# audioProto_v1.net
KiCad netlist of a schematic drawn in EAGLE
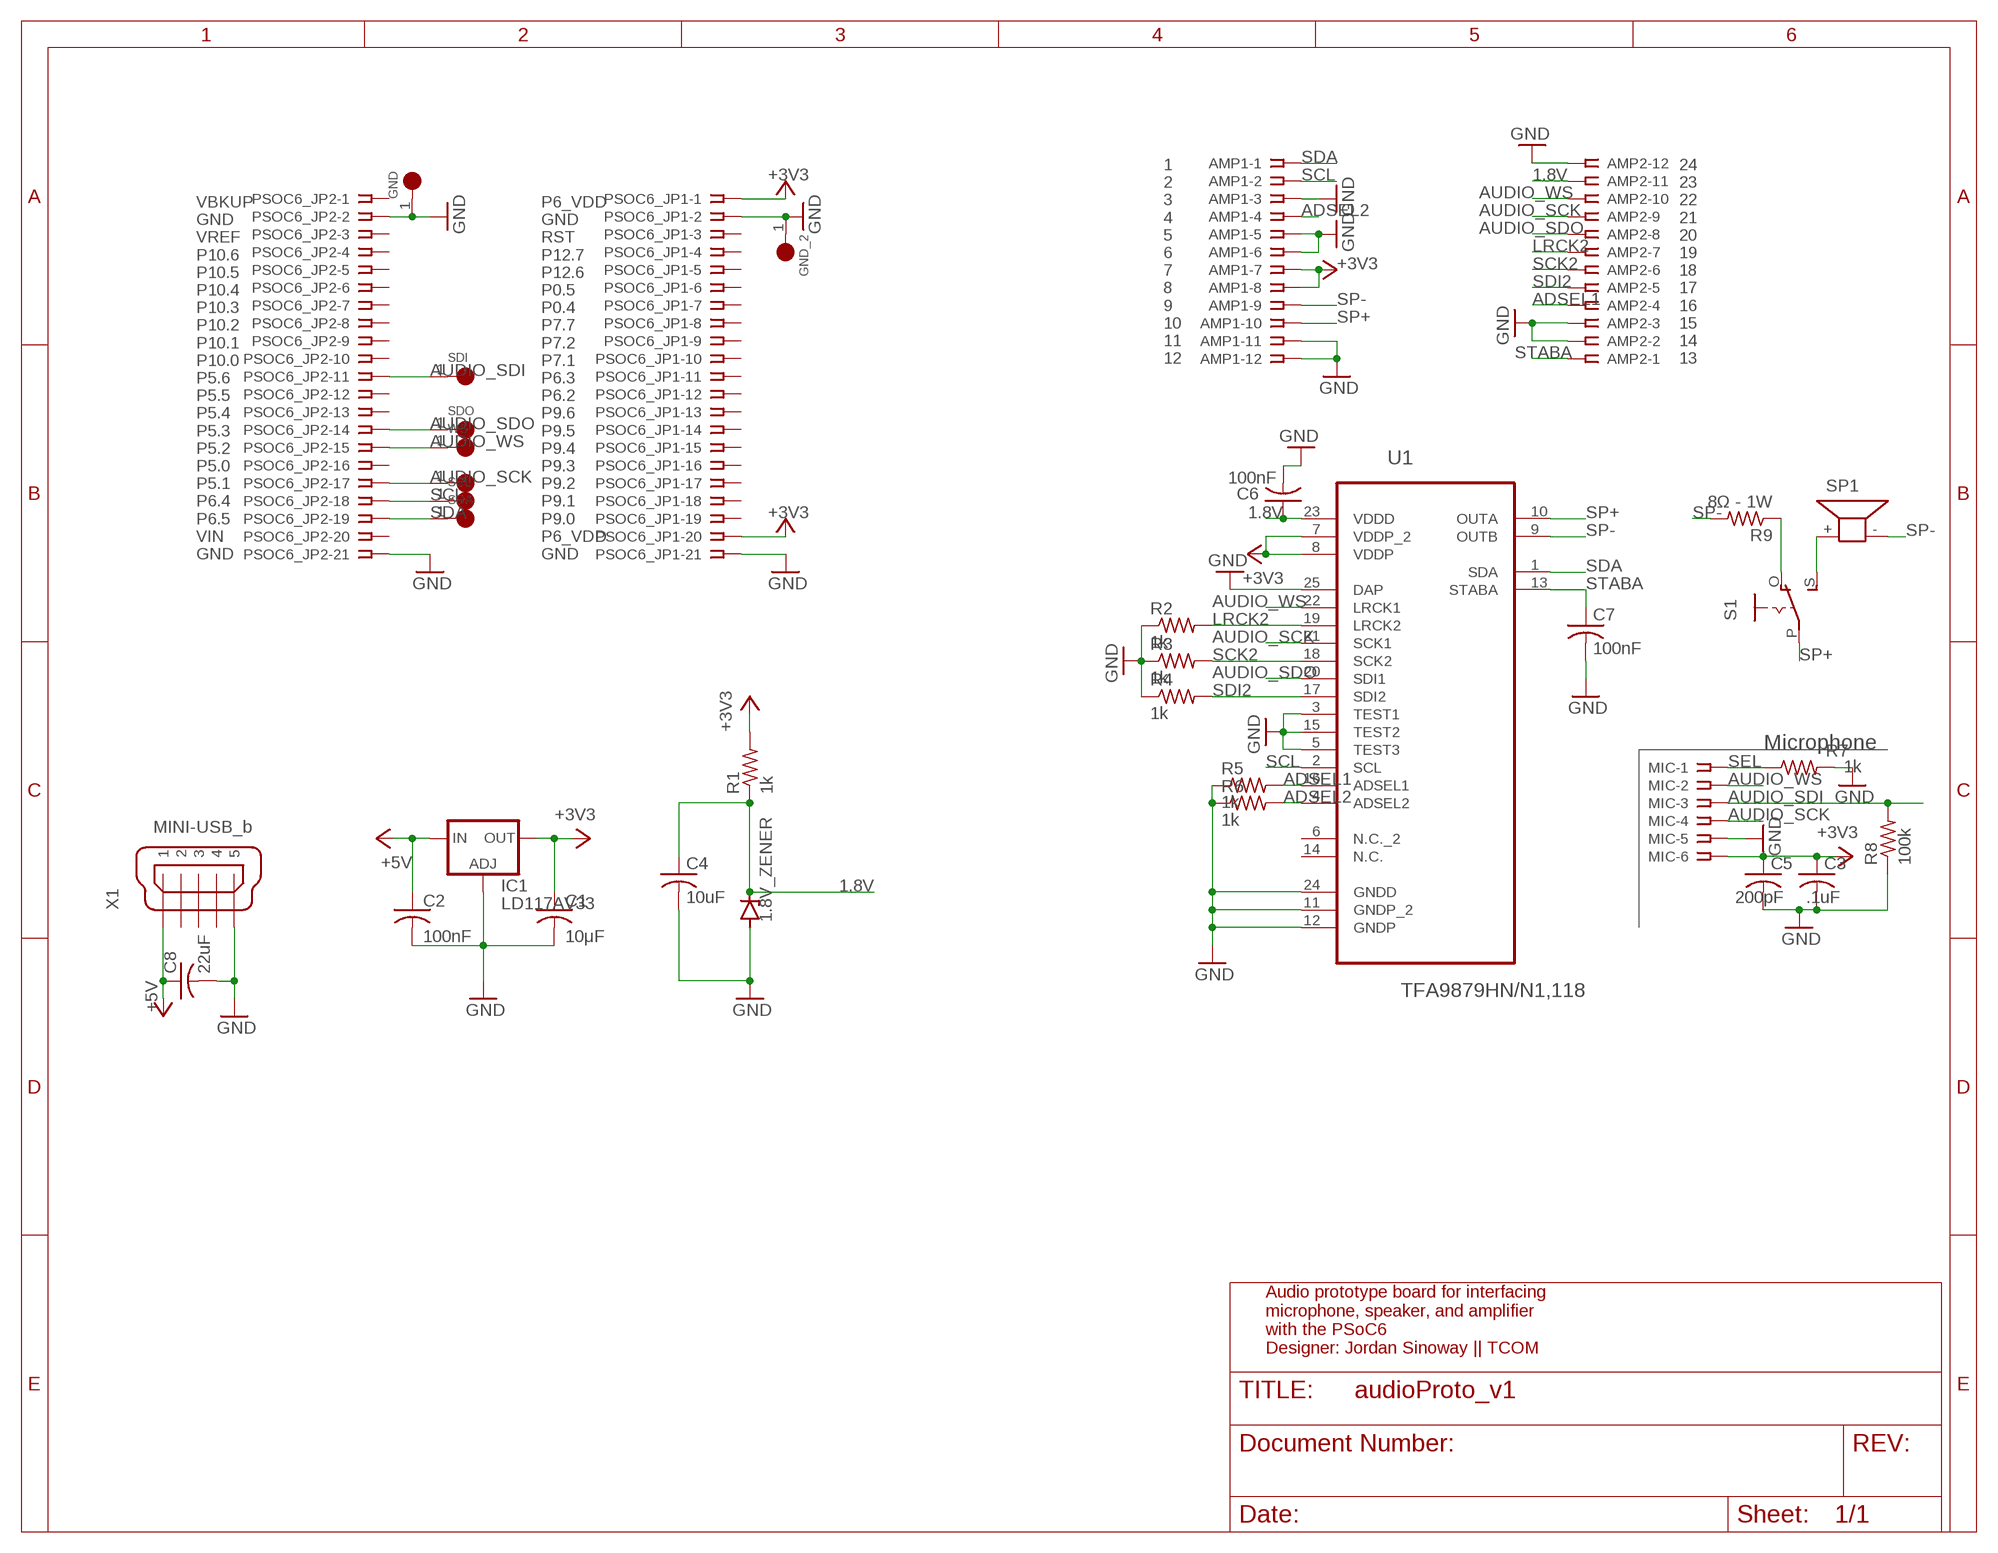
[diagram p0: schematic, sheet 1]

(export (version "E")
  (design (tool "Eeschema 10.0.6"))
  (components
    (comp (ref "1.8V_ZENER")
      (value "BZV10")
      (footprint "eagle-import:DO34Z7")
      (libsource (lib "eagle-import") (part "BZV10"))
    )
    (comp (ref "AMP1")
      (value "SSW-112-02-G-S")
      (footprint "eagle-import:SSW-112-02-G-S")
      (fields (field (name "MF") "Samtec Inc."))
      (libsource (lib "eagle-import") (part "SSW-112-02-G-S"))
    )
    (comp (ref "AMP2")
      (value "SSW-112-02-G-S")
      (footprint "eagle-import:SSW-112-02-G-S")
      (fields (field (name "MF") "Samtec Inc."))
      (libsource (lib "eagle-import") (part "SSW-112-02-G-S"))
    )
    (comp (ref "C1")
      (value "10μF")
      (footprint "eagle-import:C050-024X044")
      (libsource (lib "eagle-import") (part "C-US050-024X044"))
    )
    (comp (ref "C2")
      (value "100nF")
      (footprint "eagle-import:C050-024X044")
      (libsource (lib "eagle-import") (part "C-US050-024X044"))
    )
    (comp (ref "C3")
      (value ".1uF")
      (footprint "eagle-import:C050-024X044")
      (libsource (lib "eagle-import") (part "C-US050-024X044"))
    )
    (comp (ref "C4")
      (value "10uF")
      (footprint "eagle-import:C050-024X044")
      (libsource (lib "eagle-import") (part "C-US050-024X044"))
    )
    (comp (ref "C5")
      (value "200pF")
      (footprint "eagle-import:C050-024X044")
      (libsource (lib "eagle-import") (part "C-US050-024X044"))
    )
    (comp (ref "C6")
      (value "100nF")
      (footprint "eagle-import:C050-024X044")
      (libsource (lib "eagle-import") (part "C-US050-024X044"))
    )
    (comp (ref "C7")
      (value "100nF")
      (footprint "eagle-import:C050-024X044")
      (libsource (lib "eagle-import") (part "C-US050-024X044"))
    )
    (comp (ref "C8")
      (value "22uF")
      (footprint "eagle-import:C050-024X044")
      (libsource (lib "eagle-import") (part "C-US050-024X044"))
    )
    (comp (ref "GND")
      (value "5013")
      (footprint "eagle-import:TESTPOINT_5013")
      (fields (field (name "MF") "Keystone Electronics"))
      (libsource (lib "eagle-import") (part "5013"))
    )
    (comp (ref "GND_2")
      (value "5013")
      (footprint "eagle-import:TESTPOINT_5013")
      (fields (field (name "MF") "Keystone Electronics"))
      (libsource (lib "eagle-import") (part "5013"))
    )
    (comp (ref "IC1")
      (value "LD117AV33")
      (footprint "eagle-import:TO220L1")
      (libsource (lib "eagle-import") (part "LD117A?V33"))
    )
    (comp (ref "MIC")
      (value "SSW-106-02-G-S")
      (footprint "eagle-import:SSW-106-02-G-S")
      (fields (field (name "MF") "Samtec Inc."))
      (libsource (lib "eagle-import") (part "SSW-106-02-G-S"))
    )
    (comp (ref "PSOC6_JP1")
      (value "SSW-121-02-G-S")
      (footprint "eagle-import:SSW-121-02-G-S")
      (fields (field (name "MF") "Samtec Inc."))
      (libsource (lib "eagle-import") (part "SSW-121-02-G-S"))
    )
    (comp (ref "PSOC6_JP2")
      (value "SSW-121-02-G-S")
      (footprint "eagle-import:SSW-121-02-G-S")
      (fields (field (name "MF") "Samtec Inc."))
      (libsource (lib "eagle-import") (part "SSW-121-02-G-S"))
    )
    (comp (ref "R1")
      (value "1k")
      (footprint "eagle-import:0204_7")
      (libsource (lib "eagle-import") (part "R-US_0204/7"))
    )
    (comp (ref "R2")
      (value "1k")
      (footprint "eagle-import:0204_7")
      (libsource (lib "eagle-import") (part "R-US_0204/7"))
    )
    (comp (ref "R3")
      (value "1k")
      (footprint "eagle-import:0204_7")
      (libsource (lib "eagle-import") (part "R-US_0204/7"))
    )
    (comp (ref "R4")
      (value "1k")
      (footprint "eagle-import:0204_7")
      (libsource (lib "eagle-import") (part "R-US_0204/7"))
    )
    (comp (ref "R5")
      (value "1k")
      (footprint "eagle-import:0204_7")
      (libsource (lib "eagle-import") (part "R-US_0204/7"))
    )
    (comp (ref "R6")
      (value "1k")
      (footprint "eagle-import:0204_7")
      (libsource (lib "eagle-import") (part "R-US_0204/7"))
    )
    (comp (ref "R7")
      (value "1k")
      (footprint "eagle-import:0207_9")
      (libsource (lib "eagle-import") (part "R-US_0207/9"))
    )
    (comp (ref "R8")
      (value "100k")
      (footprint "eagle-import:0207_9")
      (libsource (lib "eagle-import") (part "R-US_0207/9"))
    )
    (comp (ref "R9")
      (value "8Ω - 1W")
      (footprint "eagle-import:0207_10")
      (libsource (lib "eagle-import") (part "R-US_0207/10"))
    )
    (comp (ref "S1")
      (value "EG1218S")
      (footprint "eagle-import:EG1218")
      (libsource (lib "eagle-import") (part "EG1218S"))
    )
    (comp (ref "SCK")
      (value "5013")
      (footprint "eagle-import:TESTPOINT_5013")
      (fields (field (name "MF") "Keystone Electronics"))
      (libsource (lib "eagle-import") (part "5013"))
    )
    (comp (ref "SCL")
      (value "5013")
      (footprint "eagle-import:TESTPOINT_5013")
      (fields (field (name "MF") "Keystone Electronics"))
      (libsource (lib "eagle-import") (part "5013"))
    )
    (comp (ref "SDA")
      (value "5013")
      (footprint "eagle-import:TESTPOINT_5013")
      (fields (field (name "MF") "Keystone Electronics"))
      (libsource (lib "eagle-import") (part "5013"))
    )
    (comp (ref "SDI")
      (value "5013")
      (footprint "eagle-import:TESTPOINT_5013")
      (fields (field (name "MF") "Keystone Electronics"))
      (libsource (lib "eagle-import") (part "5013"))
    )
    (comp (ref "SDO")
      (value "5013")
      (footprint "eagle-import:TESTPOINT_5013")
      (fields (field (name "MF") "Keystone Electronics"))
      (libsource (lib "eagle-import") (part "5013"))
    )
    (comp (ref "SP1")
      (value "KSS1201")
      (footprint "eagle-import:KSS1201")
      (libsource (lib "eagle-import") (part "KSS1201"))
    )
    (comp (ref "U1")
      (value "TFA9879HN/N1,118")
      (footprint "eagle-import:QFN50P260X260X100-25N")
      (fields (field (name "MF") "NXP USA"))
      (libsource (lib "eagle-import") (part "TFA9879HN/N1,118"))
    )
    (comp (ref "WS")
      (value "5013")
      (footprint "eagle-import:TESTPOINT_5013")
      (fields (field (name "MF") "Keystone Electronics"))
      (libsource (lib "eagle-import") (part "5013"))
    )
    (comp (ref "X1")
      (value "MINI-USB_b")
      (footprint "eagle-import:32005-601")
      (libsource (lib "eagle-import") (part "MINI-USB_SHIELD5P2-32005-601"))
    )
  )
  (nets
    (net (code "1") (name "+3V3") (class "Default")
      (node (ref "AMP1") (pin "7") (pinfunction "1_7") (pintype "passive"))
      (node (ref "AMP1") (pin "8") (pinfunction "1_8") (pintype "passive"))
      (node (ref "C1") (pin "1") (pinfunction "1_1") (pintype "passive"))
      (node (ref "C3") (pin "1") (pinfunction "1_1") (pintype "passive"))
      (node (ref "C5") (pin "1") (pinfunction "1_1") (pintype "passive"))
      (node (ref "IC1") (pin "2") (pinfunction "OUT_2") (pintype "passive"))
      (node (ref "MIC") (pin "6") (pinfunction "1_6") (pintype "passive"))
      (node (ref "PSOC6_JP1") (pin "1") (pinfunction "1_1") (pintype "passive"))
      (node (ref "PSOC6_JP1") (pin "20") (pinfunction "1_20") (pintype "passive"))
      (node (ref "R1") (pin "2") (pinfunction "2_2") (pintype "passive"))
      (node (ref "U1") (pin "7") (pinfunction "VDDP_2_7") (pintype "power_in"))
      (node (ref "U1") (pin "8") (pinfunction "VDDP_8") (pintype "power_in"))
    )
    (net (code "2") (name "+5V") (class "Default")
      (node (ref "C2") (pin "1") (pinfunction "1_1") (pintype "passive"))
      (node (ref "C8") (pin "1") (pinfunction "1_1") (pintype "passive"))
      (node (ref "IC1") (pin "3") (pinfunction "IN_3") (pintype "input"))
      (node (ref "X1") (pin "1") (pinfunction "1_1") (pintype "passive"))
    )
    (net (code "3") (name "/1.8V") (class "Default")
      (node (ref "1.8V_ZENER") (pin "C") (pinfunction "C_C") (pintype "passive"))
      (node (ref "AMP2") (pin "11") (pinfunction "1_11") (pintype "passive"))
      (node (ref "C4") (pin "1") (pinfunction "1_1") (pintype "passive"))
      (node (ref "C6") (pin "1") (pinfunction "1_1") (pintype "passive"))
      (node (ref "R1") (pin "1") (pinfunction "1_1") (pintype "passive"))
      (node (ref "U1") (pin "23") (pinfunction "VDDD_23") (pintype "power_in"))
    )
    (net (code "4") (name "/ADSEL1") (class "Default")
      (node (ref "AMP2") (pin "4") (pinfunction "1_4") (pintype "passive"))
      (node (ref "R5") (pin "2") (pinfunction "2_2") (pintype "passive"))
      (node (ref "U1") (pin "16") (pinfunction "ADSEL1_16") (pintype "input"))
    )
    (net (code "5") (name "/ADSEL2") (class "Default")
      (node (ref "AMP1") (pin "4") (pinfunction "1_4") (pintype "passive"))
      (node (ref "R6") (pin "2") (pinfunction "2_2") (pintype "passive"))
      (node (ref "U1") (pin "4") (pinfunction "ADSEL2_4") (pintype "input"))
    )
    (net (code "6") (name "/AUDIO_SCK") (class "Default")
      (node (ref "AMP2") (pin "9") (pinfunction "1_9") (pintype "passive"))
      (node (ref "MIC") (pin "4") (pinfunction "1_4") (pintype "passive"))
      (node (ref "PSOC6_JP2") (pin "17") (pinfunction "1_17") (pintype "passive"))
      (node (ref "SCK") (pin "1") (pinfunction "TP_1") (pintype "passive"))
      (node (ref "U1") (pin "21") (pinfunction "SCK1_21") (pintype "input"))
    )
    (net (code "7") (name "/AUDIO_SDI") (class "Default")
      (node (ref "MIC") (pin "3") (pinfunction "1_3") (pintype "passive"))
      (node (ref "PSOC6_JP2") (pin "11") (pinfunction "1_11") (pintype "passive"))
      (node (ref "R8") (pin "2") (pinfunction "2_2") (pintype "passive"))
      (node (ref "SDI") (pin "1") (pinfunction "TP_1") (pintype "passive"))
    )
    (net (code "8") (name "/AUDIO_SDO") (class "Default")
      (node (ref "AMP2") (pin "8") (pinfunction "1_8") (pintype "passive"))
      (node (ref "PSOC6_JP2") (pin "14") (pinfunction "1_14") (pintype "passive"))
      (node (ref "SDO") (pin "1") (pinfunction "TP_1") (pintype "passive"))
      (node (ref "U1") (pin "20") (pinfunction "SDI1_20") (pintype "input"))
    )
    (net (code "9") (name "/AUDIO_WS") (class "Default")
      (node (ref "AMP2") (pin "10") (pinfunction "1_10") (pintype "passive"))
      (node (ref "MIC") (pin "2") (pinfunction "1_2") (pintype "passive"))
      (node (ref "PSOC6_JP2") (pin "15") (pinfunction "1_15") (pintype "passive"))
      (node (ref "U1") (pin "22") (pinfunction "LRCK1_22") (pintype "input"))
      (node (ref "WS") (pin "1") (pinfunction "TP_1") (pintype "passive"))
    )
    (net (code "10") (name "/LRCK2") (class "Default")
      (node (ref "AMP2") (pin "7") (pinfunction "1_7") (pintype "passive"))
      (node (ref "R2") (pin "2") (pinfunction "2_2") (pintype "passive"))
      (node (ref "U1") (pin "19") (pinfunction "LRCK2_19") (pintype "input"))
    )
    (net (code "11") (name "/SCK2") (class "Default")
      (node (ref "AMP2") (pin "6") (pinfunction "1_6") (pintype "passive"))
      (node (ref "R3") (pin "2") (pinfunction "2_2") (pintype "passive"))
      (node (ref "U1") (pin "18") (pinfunction "SCK2_18") (pintype "input"))
    )
    (net (code "12") (name "/SCL") (class "Default")
      (node (ref "AMP1") (pin "2") (pinfunction "1_2") (pintype "passive"))
      (node (ref "PSOC6_JP2") (pin "18") (pinfunction "1_18") (pintype "passive"))
      (node (ref "SCL") (pin "1") (pinfunction "TP_1") (pintype "passive"))
      (node (ref "U1") (pin "2") (pinfunction "SCL_2") (pintype "input"))
    )
    (net (code "13") (name "/SDA") (class "Default")
      (node (ref "AMP1") (pin "1") (pinfunction "1_1") (pintype "passive"))
      (node (ref "PSOC6_JP2") (pin "19") (pinfunction "1_19") (pintype "passive"))
      (node (ref "SDA") (pin "1") (pinfunction "TP_1") (pintype "passive"))
      (node (ref "U1") (pin "1") (pinfunction "SDA_1") (pintype "bidirectional"))
    )
    (net (code "14") (name "/SDI2") (class "Default")
      (node (ref "AMP2") (pin "5") (pinfunction "1_5") (pintype "passive"))
      (node (ref "R4") (pin "2") (pinfunction "2_2") (pintype "passive"))
      (node (ref "U1") (pin "17") (pinfunction "SDI2_17") (pintype "input"))
    )
    (net (code "15") (name "/SEL") (class "Default")
      (node (ref "MIC") (pin "1") (pinfunction "1_1") (pintype "passive"))
      (node (ref "R7") (pin "1") (pinfunction "1_1") (pintype "passive"))
    )
    (net (code "16") (name "/SP+") (class "Default")
      (node (ref "AMP1") (pin "10") (pinfunction "1_10") (pintype "passive"))
      (node (ref "S1") (pin "P") (pinfunction "P_P") (pintype "passive"))
      (node (ref "U1") (pin "10") (pinfunction "OUTA_10") (pintype "output"))
    )
    (net (code "17") (name "/SP-") (class "Default")
      (node (ref "AMP1") (pin "9") (pinfunction "1_9") (pintype "passive"))
      (node (ref "R9") (pin "2") (pinfunction "2_2") (pintype "passive"))
      (node (ref "SP1") (pin "-") (pinfunction "2_-") (pintype "passive"))
      (node (ref "U1") (pin "9") (pinfunction "OUTB_9") (pintype "output"))
    )
    (net (code "18") (name "/STABA") (class "Default")
      (node (ref "AMP2") (pin "1") (pinfunction "1_1") (pintype "passive"))
      (node (ref "C7") (pin "1") (pinfunction "1_1") (pintype "passive"))
      (node (ref "U1") (pin "13") (pinfunction "STABA_13") (pintype "output"))
    )
    (net (code "19") (name "GND") (class "Default")
      (node (ref "1.8V_ZENER") (pin "A") (pinfunction "A_A") (pintype "passive"))
      (node (ref "AMP1") (pin "11") (pinfunction "1_11") (pintype "passive"))
      (node (ref "AMP1") (pin "12") (pinfunction "1_12") (pintype "passive"))
      (node (ref "AMP1") (pin "3") (pinfunction "1_3") (pintype "passive"))
      (node (ref "AMP1") (pin "5") (pinfunction "1_5") (pintype "passive"))
      (node (ref "AMP1") (pin "6") (pinfunction "1_6") (pintype "passive"))
      (node (ref "AMP2") (pin "12") (pinfunction "1_12") (pintype "passive"))
      (node (ref "AMP2") (pin "2") (pinfunction "1_2") (pintype "passive"))
      (node (ref "AMP2") (pin "3") (pinfunction "1_3") (pintype "passive"))
      (node (ref "C1") (pin "2") (pinfunction "2_2") (pintype "passive"))
      (node (ref "C2") (pin "2") (pinfunction "2_2") (pintype "passive"))
      (node (ref "C3") (pin "2") (pinfunction "2_2") (pintype "passive"))
      (node (ref "C4") (pin "2") (pinfunction "2_2") (pintype "passive"))
      (node (ref "C5") (pin "2") (pinfunction "2_2") (pintype "passive"))
      (node (ref "C6") (pin "2") (pinfunction "2_2") (pintype "passive"))
      (node (ref "C7") (pin "2") (pinfunction "2_2") (pintype "passive"))
      (node (ref "C8") (pin "2") (pinfunction "2_2") (pintype "passive"))
      (node (ref "GND") (pin "1") (pinfunction "TP_1") (pintype "passive"))
      (node (ref "GND_2") (pin "1") (pinfunction "TP_1") (pintype "passive"))
      (node (ref "IC1") (pin "1") (pinfunction "ADJ_1") (pintype "input"))
      (node (ref "MIC") (pin "5") (pinfunction "1_5") (pintype "passive"))
      (node (ref "PSOC6_JP1") (pin "2") (pinfunction "1_2") (pintype "passive"))
      (node (ref "PSOC6_JP1") (pin "21") (pinfunction "1_21") (pintype "passive"))
      (node (ref "PSOC6_JP2") (pin "2") (pinfunction "1_2") (pintype "passive"))
      (node (ref "PSOC6_JP2") (pin "21") (pinfunction "1_21") (pintype "passive"))
      (node (ref "R2") (pin "1") (pinfunction "1_1") (pintype "passive"))
      (node (ref "R3") (pin "1") (pinfunction "1_1") (pintype "passive"))
      (node (ref "R4") (pin "1") (pinfunction "1_1") (pintype "passive"))
      (node (ref "R5") (pin "1") (pinfunction "1_1") (pintype "passive"))
      (node (ref "R6") (pin "1") (pinfunction "1_1") (pintype "passive"))
      (node (ref "R7") (pin "2") (pinfunction "2_2") (pintype "passive"))
      (node (ref "R8") (pin "1") (pinfunction "1_1") (pintype "passive"))
      (node (ref "U1") (pin "11") (pinfunction "GNDP_2_11") (pintype "passive"))
      (node (ref "U1") (pin "12") (pinfunction "GNDP_12") (pintype "passive"))
      (node (ref "U1") (pin "15") (pinfunction "TEST2_15") (pintype "passive"))
      (node (ref "U1") (pin "24") (pinfunction "GNDD_24") (pintype "passive"))
      (node (ref "U1") (pin "25") (pinfunction "DAP_25") (pintype "passive"))
      (node (ref "U1") (pin "3") (pinfunction "TEST1_3") (pintype "passive"))
      (node (ref "U1") (pin "5") (pinfunction "TEST3_5") (pintype "passive"))
      (node (ref "X1") (pin "5") (pinfunction "5_5") (pintype "passive"))
    )
    (net (code "20") (name "Net-(R9-Pad1)") (class "Default")
      (node (ref "R9") (pin "1") (pinfunction "1_1") (pintype "passive"))
      (node (ref "S1") (pin "O") (pinfunction "O_O") (pintype "passive"))
    )
    (net (code "21") (name "Net-(SP1-1)") (class "Default")
      (node (ref "S1") (pin "S") (pinfunction "S_S") (pintype "passive"))
      (node (ref "SP1") (pin "+") (pinfunction "1_+") (pintype "passive"))
    )
    (net (code "22") (name "unconnected-(PSOC6_JP1B-1-Pad10)") (class "Default")
      (node (ref "PSOC6_JP1") (pin "10") (pinfunction "1_10") (pintype "passive"))
    )
    (net (code "23") (name "unconnected-(PSOC6_JP1C-1-Pad11)") (class "Default")
      (node (ref "PSOC6_JP1") (pin "11") (pinfunction "1_11") (pintype "passive"))
    )
    (net (code "24") (name "unconnected-(PSOC6_JP1D-1-Pad12)") (class "Default")
      (node (ref "PSOC6_JP1") (pin "12") (pinfunction "1_12") (pintype "passive"))
    )
    (net (code "25") (name "unconnected-(PSOC6_JP1E-1-Pad13)") (class "Default")
      (node (ref "PSOC6_JP1") (pin "13") (pinfunction "1_13") (pintype "passive"))
    )
    (net (code "26") (name "unconnected-(PSOC6_JP1F-1-Pad14)") (class "Default")
      (node (ref "PSOC6_JP1") (pin "14") (pinfunction "1_14") (pintype "passive"))
    )
    (net (code "27") (name "unconnected-(PSOC6_JP1G-1-Pad15)") (class "Default")
      (node (ref "PSOC6_JP1") (pin "15") (pinfunction "1_15") (pintype "passive"))
    )
    (net (code "28") (name "unconnected-(PSOC6_JP1H-1-Pad16)") (class "Default")
      (node (ref "PSOC6_JP1") (pin "16") (pinfunction "1_16") (pintype "passive"))
    )
    (net (code "29") (name "unconnected-(PSOC6_JP1I-1-Pad17)") (class "Default")
      (node (ref "PSOC6_JP1") (pin "17") (pinfunction "1_17") (pintype "passive"))
    )
    (net (code "30") (name "unconnected-(PSOC6_JP1J-1-Pad18)") (class "Default")
      (node (ref "PSOC6_JP1") (pin "18") (pinfunction "1_18") (pintype "passive"))
    )
    (net (code "31") (name "unconnected-(PSOC6_JP1K-1-Pad19)") (class "Default")
      (node (ref "PSOC6_JP1") (pin "19") (pinfunction "1_19") (pintype "passive"))
    )
    (net (code "32") (name "unconnected-(PSOC6_JP1O-1-Pad3)") (class "Default")
      (node (ref "PSOC6_JP1") (pin "3") (pinfunction "1_3") (pintype "passive"))
    )
    (net (code "33") (name "unconnected-(PSOC6_JP1P-1-Pad4)") (class "Default")
      (node (ref "PSOC6_JP1") (pin "4") (pinfunction "1_4") (pintype "passive"))
    )
    (net (code "34") (name "unconnected-(PSOC6_JP1Q-1-Pad5)") (class "Default")
      (node (ref "PSOC6_JP1") (pin "5") (pinfunction "1_5") (pintype "passive"))
    )
    (net (code "35") (name "unconnected-(PSOC6_JP1R-1-Pad6)") (class "Default")
      (node (ref "PSOC6_JP1") (pin "6") (pinfunction "1_6") (pintype "passive"))
    )
    (net (code "36") (name "unconnected-(PSOC6_JP1S-1-Pad7)") (class "Default")
      (node (ref "PSOC6_JP1") (pin "7") (pinfunction "1_7") (pintype "passive"))
    )
    (net (code "37") (name "unconnected-(PSOC6_JP1T-1-Pad8)") (class "Default")
      (node (ref "PSOC6_JP1") (pin "8") (pinfunction "1_8") (pintype "passive"))
    )
    (net (code "38") (name "unconnected-(PSOC6_JP1U-1-Pad9)") (class "Default")
      (node (ref "PSOC6_JP1") (pin "9") (pinfunction "1_9") (pintype "passive"))
    )
    (net (code "39") (name "unconnected-(PSOC6_JP2-Pad1)") (class "Default")
      (node (ref "PSOC6_JP2") (pin "1") (pinfunction "1_1") (pintype "passive"))
    )
    (net (code "40") (name "unconnected-(PSOC6_JP2B-1-Pad10)") (class "Default")
      (node (ref "PSOC6_JP2") (pin "10") (pinfunction "1_10") (pintype "passive"))
    )
    (net (code "41") (name "unconnected-(PSOC6_JP2D-1-Pad12)") (class "Default")
      (node (ref "PSOC6_JP2") (pin "12") (pinfunction "1_12") (pintype "passive"))
    )
    (net (code "42") (name "unconnected-(PSOC6_JP2E-1-Pad13)") (class "Default")
      (node (ref "PSOC6_JP2") (pin "13") (pinfunction "1_13") (pintype "passive"))
    )
    (net (code "43") (name "unconnected-(PSOC6_JP2H-1-Pad16)") (class "Default")
      (node (ref "PSOC6_JP2") (pin "16") (pinfunction "1_16") (pintype "passive"))
    )
    (net (code "44") (name "unconnected-(PSOC6_JP2M-1-Pad20)") (class "Default")
      (node (ref "PSOC6_JP2") (pin "20") (pinfunction "1_20") (pintype "passive"))
    )
    (net (code "45") (name "unconnected-(PSOC6_JP2O-1-Pad3)") (class "Default")
      (node (ref "PSOC6_JP2") (pin "3") (pinfunction "1_3") (pintype "passive"))
    )
    (net (code "46") (name "unconnected-(PSOC6_JP2P-1-Pad4)") (class "Default")
      (node (ref "PSOC6_JP2") (pin "4") (pinfunction "1_4") (pintype "passive"))
    )
    (net (code "47") (name "unconnected-(PSOC6_JP2Q-1-Pad5)") (class "Default")
      (node (ref "PSOC6_JP2") (pin "5") (pinfunction "1_5") (pintype "passive"))
    )
    (net (code "48") (name "unconnected-(PSOC6_JP2R-1-Pad6)") (class "Default")
      (node (ref "PSOC6_JP2") (pin "6") (pinfunction "1_6") (pintype "passive"))
    )
    (net (code "49") (name "unconnected-(PSOC6_JP2S-1-Pad7)") (class "Default")
      (node (ref "PSOC6_JP2") (pin "7") (pinfunction "1_7") (pintype "passive"))
    )
    (net (code "50") (name "unconnected-(PSOC6_JP2T-1-Pad8)") (class "Default")
      (node (ref "PSOC6_JP2") (pin "8") (pinfunction "1_8") (pintype "passive"))
    )
    (net (code "51") (name "unconnected-(PSOC6_JP2U-1-Pad9)") (class "Default")
      (node (ref "PSOC6_JP2") (pin "9") (pinfunction "1_9") (pintype "passive"))
    )
    (net (code "52") (name "unconnected-(U1-N.C.-Pad14)") (class "Default")
      (node (ref "U1") (pin "14") (pinfunction "N.C._14") (pintype "no_connect"))
    )
    (net (code "53") (name "unconnected-(U1-N.C._2-Pad6)") (class "Default")
      (node (ref "U1") (pin "6") (pinfunction "N.C._2_6") (pintype "no_connect"))
    )
    (net (code "54") (name "unconnected-(X1-Pad2)") (class "Default")
      (node (ref "X1") (pin "2") (pinfunction "2_2") (pintype "passive"))
    )
    (net (code "55") (name "unconnected-(X1-Pad3)") (class "Default")
      (node (ref "X1") (pin "3") (pinfunction "3_3") (pintype "passive"))
    )
    (net (code "56") (name "unconnected-(X1-Pad4)") (class "Default")
      (node (ref "X1") (pin "4") (pinfunction "4_4") (pintype "passive"))
    )
  )
)
